# Chov3_main.net
KiCad netlist of a schematic drawn in Altium Designer
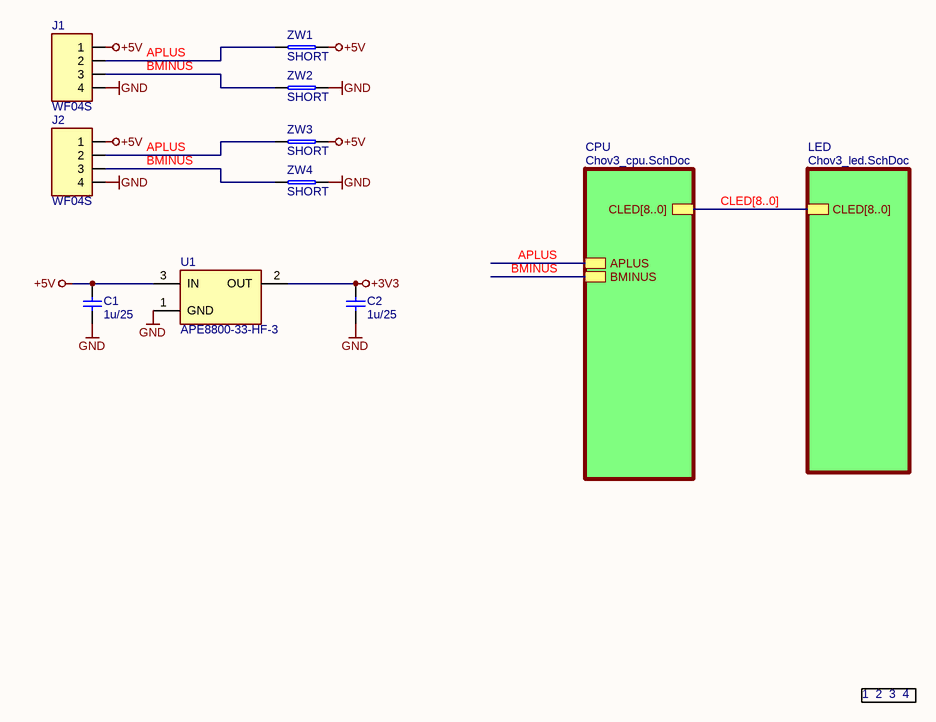
[diagram p0: Chov3_main.SchDoc]

(export (version "E")
  (design (tool "Eeschema 10.0.6"))
  (components
    (comp (ref "C1")
      (value "CL21B105KAFNNNG")
      (footprint "0805")
      (fields (field (name "OTHERPARAMS") "1u/25") (field (name "TOLERANCE") "10%"))
      (libsource (lib "Parts") (part "C"))
    )
    (comp (ref "C2")
      (value "CL21B105KAFNNNG")
      (footprint "0805")
      (fields (field (name "OTHERPARAMS") "1u/25") (field (name "TOLERANCE") "10%"))
      (libsource (lib "Parts") (part "C"))
    )
    (comp (ref "J1") (value "WF04S") (footprint "WF04S") (libsource (lib "Parts") (part "HEADER4")))
    (comp (ref "J2") (value "WF04S") (footprint "WF04S") (libsource (lib "Parts") (part "HEADER4")))
    (comp (ref "NUMBERS1")
      (value "WARSTWYT_M1_M2_B")
      (footprint "WARSTWYT_M1_M2_B")
      (libsource (lib "Parts") (part "NUMBERSLAYERS_T_M1_M2_B"))
    )
    (comp (ref "U1")
      (value "APE8800-33-HF-3")
      (footprint "SOT23-3")
      (libsource (lib "Parts") (part "MCP1700"))
    )
    (comp (ref "ZW1")
      (value "SHORT")
      (footprint "SHORT0805")
      (fields (field (name "TOLERANCE") "1%"))
      (libsource (lib "Parts") (part "SHORT"))
    )
    (comp (ref "ZW2")
      (value "SHORT")
      (footprint "SHORT0805")
      (fields (field (name "TOLERANCE") "1%"))
      (libsource (lib "Parts") (part "SHORT"))
    )
    (comp (ref "ZW3")
      (value "SHORT")
      (footprint "SHORT0805")
      (fields (field (name "TOLERANCE") "1%"))
      (libsource (lib "Parts") (part "SHORT"))
    )
    (comp (ref "ZW4")
      (value "SHORT")
      (footprint "SHORT0805")
      (fields (field (name "TOLERANCE") "1%"))
      (libsource (lib "Parts") (part "SHORT"))
    )
  )
  (nets
    (net (code "10") (name "+3V3") (class "Default")
      (node (ref "C2") (pin "1") (pinfunction "1_1") (pintype "passive"))
      (node (ref "U1") (pin "2") (pinfunction "OUT_2") (pintype "passive"))
    )
    (net (code "11") (name "+5V") (class "Default")
      (node (ref "C1") (pin "1") (pinfunction "1_1") (pintype "passive"))
      (node (ref "J1") (pin "1") (pinfunction "1_1") (pintype "passive"))
      (node (ref "J2") (pin "1") (pinfunction "1_1") (pintype "passive"))
      (node (ref "U1") (pin "3") (pinfunction "IN_3") (pintype "passive"))
      (node (ref "ZW1") (pin "2") (pinfunction "2_2") (pintype "passive"))
      (node (ref "ZW3") (pin "2") (pinfunction "2_2") (pintype "passive"))
    )
    (net (code "12") (name "/APLUS") (class "Default")
      (node (ref "J1") (pin "2") (pinfunction "2_2") (pintype "passive"))
      (node (ref "J2") (pin "2") (pinfunction "2_2") (pintype "passive"))
      (node (ref "ZW1") (pin "1") (pinfunction "1_1") (pintype "passive"))
      (node (ref "ZW3") (pin "1") (pinfunction "1_1") (pintype "passive"))
    )
    (net (code "13") (name "/BMINUS") (class "Default")
      (node (ref "J1") (pin "3") (pinfunction "3_3") (pintype "passive"))
      (node (ref "J2") (pin "3") (pinfunction "3_3") (pintype "passive"))
      (node (ref "ZW2") (pin "1") (pinfunction "1_1") (pintype "passive"))
      (node (ref "ZW4") (pin "1") (pinfunction "1_1") (pintype "passive"))
    )
    (net (code "15") (name "GND") (class "Default")
      (node (ref "C1") (pin "2") (pinfunction "2_2") (pintype "passive"))
      (node (ref "C2") (pin "2") (pinfunction "2_2") (pintype "passive"))
      (node (ref "J1") (pin "4") (pinfunction "4_4") (pintype "passive"))
      (node (ref "J2") (pin "4") (pinfunction "4_4") (pintype "passive"))
      (node (ref "U1") (pin "1") (pinfunction "GND_1") (pintype "passive"))
      (node (ref "ZW2") (pin "2") (pinfunction "2_2") (pintype "passive"))
      (node (ref "ZW4") (pin "2") (pinfunction "2_2") (pintype "passive"))
    )
  )
)
